# Ampli4.net
KiCad netlist of a schematic drawn in Altium Designer
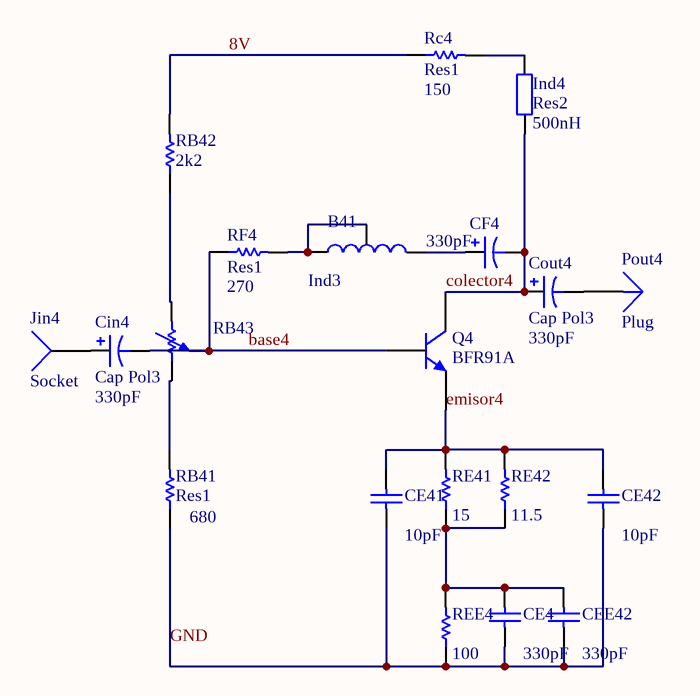
[diagram p0: Ampli4.SchDoc]

(export (version "E")
  (design (tool "Eeschema 10.0.6"))
  (components
    (comp (ref "B41") (value "Ind3") (footprint "Ind 7mm") (libsource (lib "epf") (part "Ind3")))
    (comp (ref "CE4")
      (value "330pF")
      (footprint "1608[0603]")
      (description "Capacitor (Semiconductor SIM Model)")
      (fields (field (name "Comment") "Cap Semi") (field (name "PUBLISHER") "Altium Limited"))
      (libsource (lib "Miscellaneous Devices") (part "Cap Semi"))
    )
    (comp (ref "CE41")
      (value "10pF")
      (footprint "1608[0603]")
      (description "Capacitor (Semiconductor SIM Model)")
      (fields (field (name "Comment") "Cap Semi") (field (name "PUBLISHER") "Altium Limited"))
      (libsource (lib "Miscellaneous Devices") (part "Cap Semi"))
    )
    (comp (ref "CE42")
      (value "10pF")
      (footprint "1608[0603]")
      (description "Capacitor (Semiconductor SIM Model)")
      (fields (field (name "Comment") "Cap Semi") (field (name "PUBLISHER") "Altium Limited"))
      (libsource (lib "Miscellaneous Devices") (part "Cap Semi"))
    )
    (comp (ref "CEE42")
      (value "330pF")
      (footprint "1608[0603]")
      (description "Capacitor (Semiconductor SIM Model)")
      (fields (field (name "Comment") "Cap Semi") (field (name "PUBLISHER") "Altium Limited"))
      (libsource (lib "Miscellaneous Devices") (part "Cap Semi"))
    )
    (comp (ref "CF4")
      (value "330pF")
      (footprint "C0805")
      (description "Polarized Capacitor (Surface Mount)")
      (fields (field (name "Comment") "Cap Pol3") (field (name "PUBLISHER") "Altium Limited"))
      (libsource (lib "Miscellaneous Devices") (part "Cap Pol3"))
    )
    (comp (ref "Cin4")
      (value "Cap Pol3")
      (footprint "C0805")
      (description "Polarized Capacitor (Surface Mount)")
      (fields (field (name "ALTIUM_VALUE") "330pF") (field (name "PUBLISHER") "Altium Limited"))
      (libsource (lib "Miscellaneous Devices") (part "Cap Pol3"))
    )
    (comp (ref "Cout4")
      (value "Cap Pol3")
      (footprint "C0805")
      (description "Polarized Capacitor (Surface Mount)")
      (fields (field (name "ALTIUM_VALUE") "330pF") (field (name "PUBLISHER") "Altium Limited"))
      (libsource (lib "Miscellaneous Devices") (part "Cap Pol3"))
    )
    (comp (ref "Ind4")
      (value "Res2")
      (footprint "AXIAL-0.4")
      (description "Resistor")
      (fields (field (name "ALTIUM_VALUE") "500nH") (field (name "PUBLISHER") "Altium Limited"))
      (libsource (lib "Miscellaneous Devices") (part "Res2"))
    )
    (comp (ref "Jin4")
      (value "Socket")
      (footprint "PIN1")
      (fields (field (name "PUBLISHER") "Altium Limited"))
      (libsource (lib "Miscellaneous Connectors") (part "Socket"))
    )
    (comp (ref "Pout4")
      (value "Plug")
      (footprint "PIN1")
      (fields (field (name "PUBLISHER") "Altium Limited"))
      (libsource (lib "Miscellaneous Connectors") (part "Plug"))
    )
    (comp (ref "Q4")
      (value "BFR91A")
      (footprint "SOT-37_short")
      (description "NPN 5 GHz Wideband Transistor")
      (fields (field (name "PUBLISHER") "Altium Limited"))
      (libsource (lib "Philips Discrete BJT - RF Transistor") (part "BFR92A"))
    )
    (comp (ref "RB41")
      (value "Res1")
      (footprint "AXIAL-0.3")
      (description "Resistor")
      (fields (field (name "ALTIUM_VALUE") "680") (field (name "PUBLISHER") "Altium Limited"))
      (libsource (lib "Miscellaneous Devices") (part "Res1"))
    )
    (comp (ref "RB42")
      (value "2k2")
      (footprint "AXIAL-0.3")
      (description "Resistor")
      (fields (field (name "Comment") "Res1") (field (name "PUBLISHER") "Altium Limited"))
      (libsource (lib "Miscellaneous Devices") (part "Res1"))
    )
    (comp (ref "RB43") (value "Pot") (footprint "Potenciometro") (libsource (lib "epf") (part "Pot")))
    (comp (ref "Rc4")
      (value "Res1")
      (footprint "AXIAL-0.3")
      (description "Resistor")
      (fields (field (name "ALTIUM_VALUE") "150") (field (name "PUBLISHER") "Altium Limited"))
      (libsource (lib "Miscellaneous Devices") (part "Res1"))
    )
    (comp (ref "RE41")
      (value "15")
      (footprint "1608[0603]")
      (description "Semiconductor Resistor")
      (fields (field (name "Comment") "Res Semi") (field (name "PUBLISHER") "Altium Limited"))
      (libsource (lib "Miscellaneous Devices") (part "Res Semi"))
    )
    (comp (ref "RE42")
      (value "11.5")
      (footprint "2012[0805]")
      (description "Semiconductor Resistor")
      (fields (field (name "Comment") "Res Semi") (field (name "PUBLISHER") "Altium Limited"))
      (libsource (lib "Miscellaneous Devices") (part "Res Semi"))
    )
    (comp (ref "REE4")
      (value "100")
      (footprint "2012[0805]")
      (description "Semiconductor Resistor")
      (fields (field (name "Comment") "Res Semi") (field (name "PUBLISHER") "Altium Limited"))
      (libsource (lib "Miscellaneous Devices") (part "Res Semi"))
    )
    (comp (ref "RF4")
      (value "Res1")
      (footprint "AXIAL-0.3")
      (description "Resistor")
      (fields (field (name "ALTIUM_VALUE") "270") (field (name "PUBLISHER") "Altium Limited"))
      (libsource (lib "Miscellaneous Devices") (part "Res1"))
    )
  )
  (nets
    (net (code "1") (name "/8V") (class "Default")
      (node (ref "RB42") (pin "2") (pinfunction "2_2") (pintype "passive"))
      (node (ref "Rc4") (pin "1") (pinfunction "1_1") (pintype "passive"))
    )
    (net (code "2") (name "/GND") (class "Default")
      (node (ref "CE4") (pin "1") (pinfunction "1_1") (pintype "passive"))
      (node (ref "CE41") (pin "1") (pinfunction "1_1") (pintype "passive"))
      (node (ref "CE42") (pin "1") (pinfunction "1_1") (pintype "passive"))
      (node (ref "CEE42") (pin "1") (pinfunction "1_1") (pintype "passive"))
      (node (ref "RB41") (pin "1") (pinfunction "1_1") (pintype "passive"))
      (node (ref "REE4") (pin "1") (pinfunction "1_1") (pintype "passive"))
    )
    (net (code "3") (name "/base4") (class "Default")
      (node (ref "Cin4") (pin "2") (pinfunction "2_2") (pintype "passive"))
      (node (ref "Q4") (pin "0") (pinfunction "B_0") (pintype "passive"))
      (node (ref "RB43") (pin "3") (pinfunction "3_3") (pintype "passive"))
      (node (ref "RF4") (pin "1") (pinfunction "1_1") (pintype "passive"))
    )
    (net (code "4") (name "/colector4") (class "Default")
      (node (ref "CF4") (pin "2") (pinfunction "2_2") (pintype "passive"))
      (node (ref "Cout4") (pin "1") (pinfunction "1_1") (pintype "passive"))
      (node (ref "Ind4") (pin "1") (pinfunction "1_1") (pintype "passive"))
      (node (ref "Q4") (pin "2") (pinfunction "C_2") (pintype "passive"))
    )
    (net (code "5") (name "/emisor4") (class "Default")
      (node (ref "CE41") (pin "2") (pinfunction "2_2") (pintype "passive"))
      (node (ref "CE42") (pin "2") (pinfunction "2_2") (pintype "passive"))
      (node (ref "Q4") (pin "1") (pinfunction "E_1") (pintype "passive"))
      (node (ref "RE41") (pin "2") (pinfunction "2_2") (pintype "passive"))
      (node (ref "RE42") (pin "2") (pinfunction "2_2") (pintype "passive"))
    )
    (net (code "6") (name "Net-(B41-Pad0)") (class "Default")
      (node (ref "B41") (pin "0") (pinfunction "0_0") (pintype "passive"))
      (node (ref "B41") (pin "2") (pinfunction "2_2") (pintype "passive"))
      (node (ref "RF4") (pin "2") (pinfunction "2_2") (pintype "passive"))
    )
    (net (code "7") (name "Net-(B41-Pad1)") (class "Default")
      (node (ref "B41") (pin "1") (pinfunction "1_1") (pintype "passive"))
      (node (ref "CF4") (pin "1") (pinfunction "1_1") (pintype "passive"))
    )
    (net (code "8") (name "Net-(CE4-Pad2)") (class "Default")
      (node (ref "CE4") (pin "2") (pinfunction "2_2") (pintype "passive"))
      (node (ref "CEE42") (pin "2") (pinfunction "2_2") (pintype "passive"))
      (node (ref "RE41") (pin "1") (pinfunction "1_1") (pintype "passive"))
      (node (ref "RE42") (pin "1") (pinfunction "1_1") (pintype "passive"))
      (node (ref "REE4") (pin "2") (pinfunction "2_2") (pintype "passive"))
    )
    (net (code "9") (name "Net-(Cin4-Pad1)") (class "Default")
      (node (ref "Cin4") (pin "1") (pinfunction "1_1") (pintype "passive"))
      (node (ref "Jin4") (pin "1") (pinfunction "1_1") (pintype "passive"))
    )
    (net (code "10") (name "Net-(Cout4-Pad2)") (class "Default")
      (node (ref "Cout4") (pin "2") (pinfunction "2_2") (pintype "passive"))
      (node (ref "Pout4") (pin "1") (pinfunction "1_1") (pintype "passive"))
    )
    (net (code "11") (name "Net-(Ind4-Pad2)") (class "Default")
      (node (ref "Ind4") (pin "2") (pinfunction "2_2") (pintype "passive"))
      (node (ref "Rc4") (pin "2") (pinfunction "2_2") (pintype "passive"))
    )
    (net (code "12") (name "Net-(RB41-Pad2)") (class "Default")
      (node (ref "RB41") (pin "2") (pinfunction "2_2") (pintype "passive"))
      (node (ref "RB43") (pin "2") (pinfunction "2_2") (pintype "passive"))
    )
    (net (code "13") (name "Net-(RB42-Pad1)") (class "Default")
      (node (ref "RB42") (pin "1") (pinfunction "1_1") (pintype "passive"))
      (node (ref "RB43") (pin "1") (pinfunction "1_1") (pintype "passive"))
    )
  )
)
